# a78-flashcart-plus.net
KiCad netlist of a schematic drawn in EAGLE
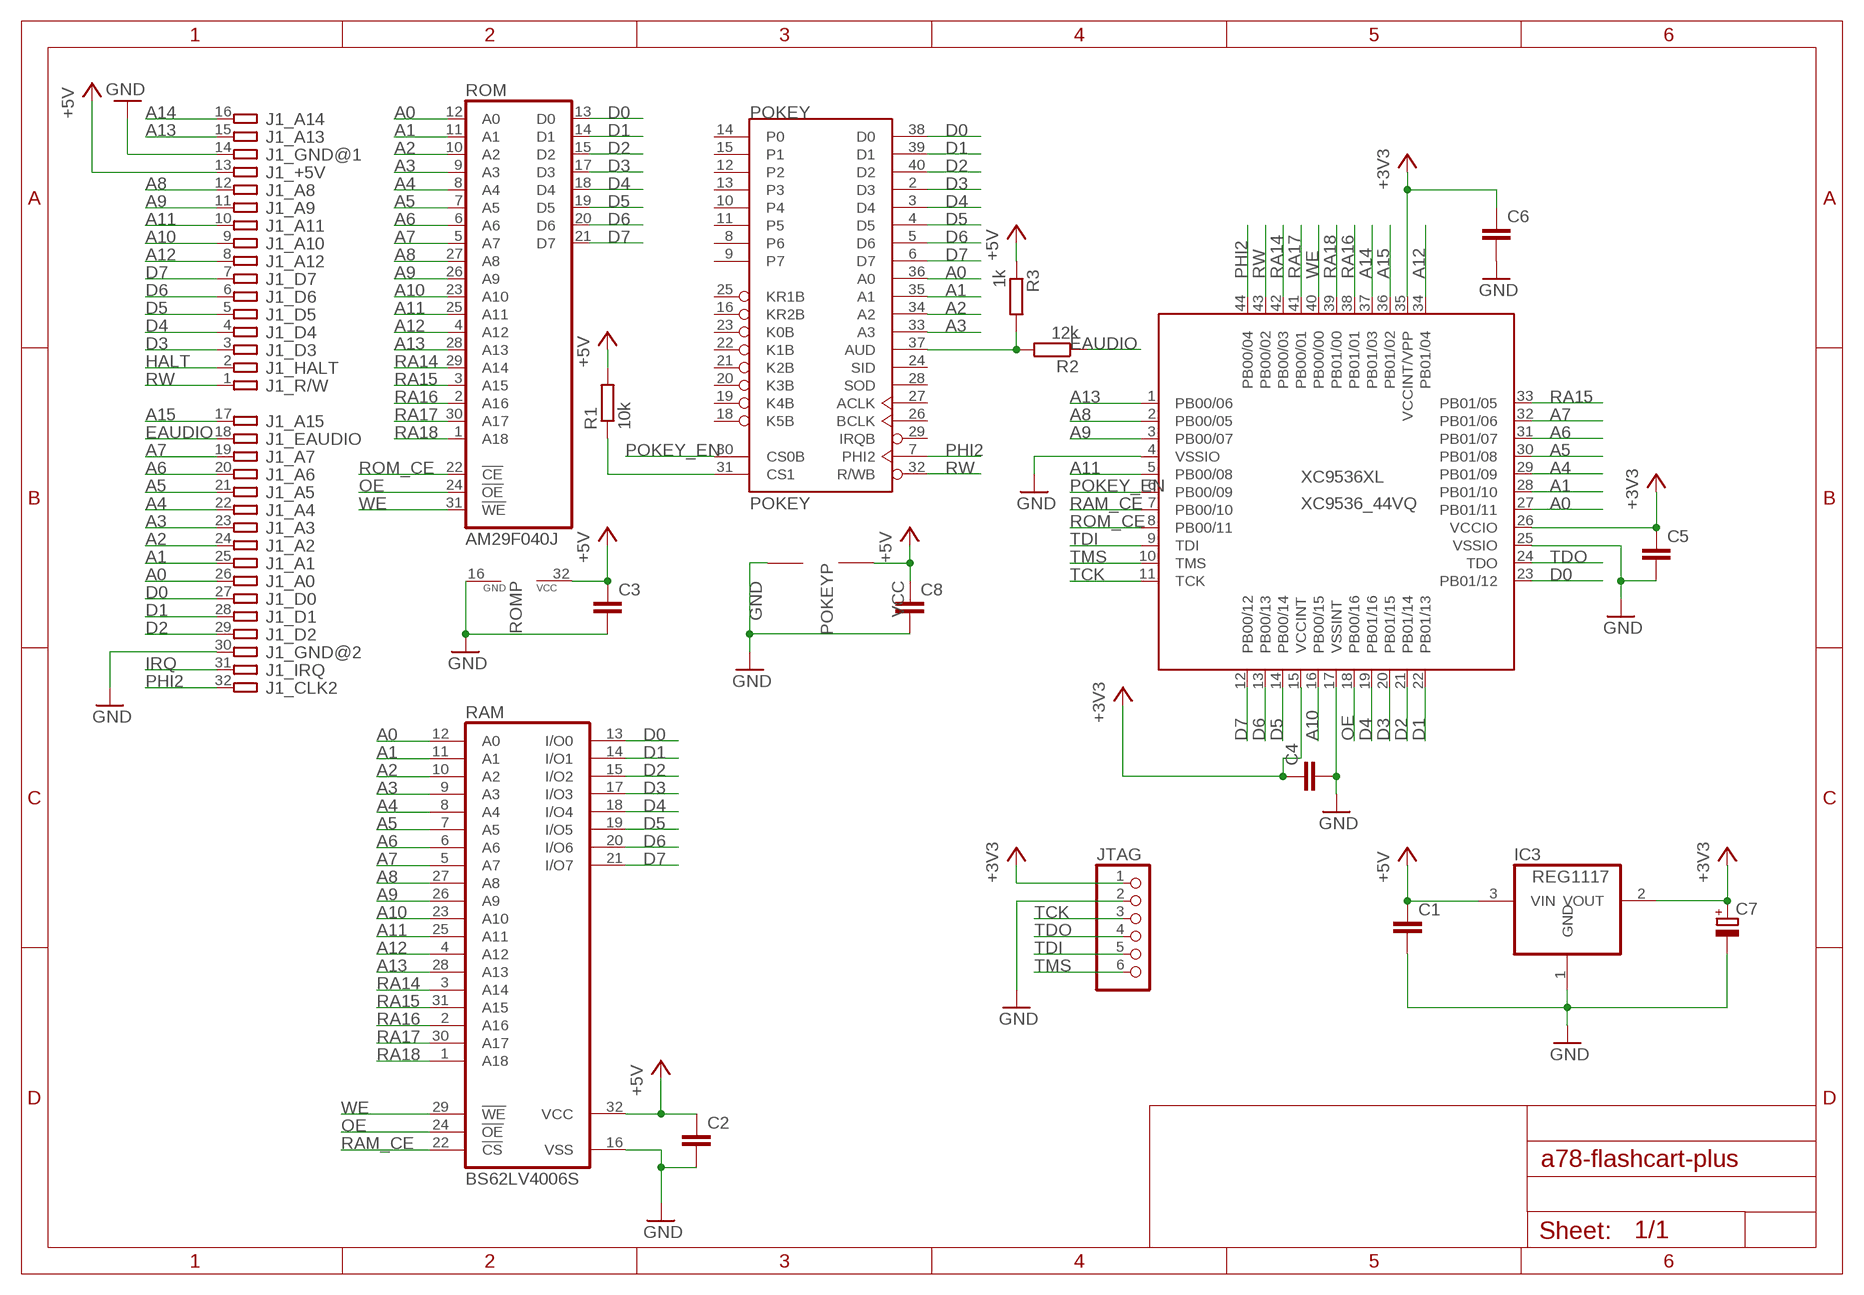
[diagram p0: schematic, sheet 1]

(export (version "E")
  (design (tool "Eeschema 10.0.6"))
  (components
    (comp (ref "C1")
      (value "C-EUC0603")
      (footprint "eagle-import:C0603")
      (libsource (lib "eagle-import") (part "C-EUC0603"))
    )
    (comp (ref "C2")
      (value "C-EUC0603")
      (footprint "eagle-import:C0603")
      (libsource (lib "eagle-import") (part "C-EUC0603"))
    )
    (comp (ref "C3")
      (value "C-EUC0603")
      (footprint "eagle-import:C0603")
      (libsource (lib "eagle-import") (part "C-EUC0603"))
    )
    (comp (ref "C4")
      (value "C-EUC0603")
      (footprint "eagle-import:C0603")
      (libsource (lib "eagle-import") (part "C-EUC0603"))
    )
    (comp (ref "C5")
      (value "C-EUC0603")
      (footprint "eagle-import:C0603")
      (libsource (lib "eagle-import") (part "C-EUC0603"))
    )
    (comp (ref "C6")
      (value "C-EUC0603")
      (footprint "eagle-import:C0603")
      (libsource (lib "eagle-import") (part "C-EUC0603"))
    )
    (comp (ref "C7")
      (value "CPOL-EUSMCC")
      (footprint "eagle-import:SMC_C")
      (libsource (lib "eagle-import") (part "CPOL-EUSMCC"))
    )
    (comp (ref "C8")
      (value "C-EUC0603")
      (footprint "eagle-import:C0603")
      (libsource (lib "eagle-import") (part "C-EUC0603"))
    )
    (comp (ref "IC3")
      (value "REG1117")
      (footprint "eagle-import:SOT223")
      (libsource (lib "eagle-import") (part "REG1117"))
    )
    (comp (ref "J1")
      (value "ATARI-7800-LARGE")
      (footprint "eagle-import:ATARI-7800-LARGE")
      (libsource (lib "eagle-import") (part "ATARI-7800-LARGE"))
    )
    (comp (ref "JTAG")
      (value "PINHD-1X6")
      (footprint "eagle-import:1X06")
      (libsource (lib "eagle-import") (part "PINHD-1X6"))
    )
    (comp (ref "POKEY")
      (value "POKEY")
      (footprint "eagle-import:DIL40")
      (libsource (lib "eagle-import") (part "POKEY"))
    )
    (comp (ref "R1")
      (value "10k")
      (footprint "eagle-import:R0603")
      (libsource (lib "eagle-import") (part "R-EU_R0603"))
    )
    (comp (ref "R2")
      (value "12k")
      (footprint "eagle-import:R0603")
      (libsource (lib "eagle-import") (part "R-EU_R0603"))
    )
    (comp (ref "R3")
      (value "1k")
      (footprint "eagle-import:R0603")
      (libsource (lib "eagle-import") (part "R-EU_R0603"))
    )
    (comp (ref "RAM")
      (value "BS62LV4006S")
      (footprint "eagle-import:SOP-32")
      (libsource (lib "eagle-import") (part "BS62LV4006S"))
    )
    (comp (ref "ROM")
      (value "AM29F040J")
      (footprint "eagle-import:PLCC32R")
      (libsource (lib "eagle-import") (part "AM29F040J"))
    )
    (comp (ref "XC9536XL")
      (value "XC9536_44VQ")
      (footprint "eagle-import:SQFP-S-10X10-44")
      (fields (field (name "MPN") "XC9536-15VQG44C"))
      (libsource (lib "eagle-import") (part "XC9536_44VQ"))
    )
  )
  (nets
    (net (code "1") (name "+3V3") (class "Default")
      (node (ref "C4") (pin "1") (pinfunction "1_1") (pintype "passive"))
      (node (ref "C5") (pin "1") (pinfunction "1_1") (pintype "passive"))
      (node (ref "C6") (pin "1") (pinfunction "1_1") (pintype "passive"))
      (node (ref "C7") (pin "+") (pinfunction "+_+") (pintype "passive"))
      (node (ref "IC3") (pin "2") (pinfunction "VOUT_2") (pintype "output"))
      (node (ref "JTAG") (pin "1") (pinfunction "1_1") (pintype "passive"))
      (node (ref "XC9536XL") (pin "15") (pinfunction "VCCINT_15") (pintype "power_in"))
      (node (ref "XC9536XL") (pin "26") (pinfunction "VCCIO_26") (pintype "power_in"))
      (node (ref "XC9536XL") (pin "35") (pinfunction "VCCINT/VPP_35") (pintype "input"))
    )
    (net (code "2") (name "+5V") (class "Default")
      (node (ref "C1") (pin "1") (pinfunction "1_1") (pintype "passive"))
      (node (ref "C2") (pin "1") (pinfunction "1_1") (pintype "passive"))
      (node (ref "C3") (pin "1") (pinfunction "1_1") (pintype "passive"))
      (node (ref "C8") (pin "1") (pinfunction "1_1") (pintype "passive"))
      (node (ref "IC3") (pin "3") (pinfunction "VIN_3") (pintype "input"))
      (node (ref "J1") (pin "13") (pinfunction "P_13") (pintype "bidirectional"))
      (node (ref "POKEY") (pin "17") (pinfunction "VCC_17") (pintype "power_in"))
      (node (ref "R1") (pin "2") (pinfunction "2_2") (pintype "passive"))
      (node (ref "R3") (pin "1") (pinfunction "1_1") (pintype "passive"))
      (node (ref "RAM") (pin "32") (pinfunction "VCC_32") (pintype "power_in"))
      (node (ref "ROM") (pin "32") (pinfunction "VCC_32") (pintype "power_in"))
    )
    (net (code "3") (name "/A0") (class "Default")
      (node (ref "J1") (pin "26") (pinfunction "P_26") (pintype "bidirectional"))
      (node (ref "POKEY") (pin "36") (pinfunction "A0_36") (pintype "bidirectional"))
      (node (ref "RAM") (pin "12") (pinfunction "A0_12") (pintype "input"))
      (node (ref "ROM") (pin "12") (pinfunction "A0_12") (pintype "input"))
      (node (ref "XC9536XL") (pin "27") (pinfunction "PB01/11_27") (pintype "bidirectional"))
    )
    (net (code "4") (name "/A1") (class "Default")
      (node (ref "J1") (pin "25") (pinfunction "P_25") (pintype "bidirectional"))
      (node (ref "POKEY") (pin "35") (pinfunction "A1_35") (pintype "bidirectional"))
      (node (ref "RAM") (pin "11") (pinfunction "A1_11") (pintype "input"))
      (node (ref "ROM") (pin "11") (pinfunction "A1_11") (pintype "input"))
      (node (ref "XC9536XL") (pin "28") (pinfunction "PB01/10_28") (pintype "bidirectional"))
    )
    (net (code "5") (name "/A2") (class "Default")
      (node (ref "J1") (pin "24") (pinfunction "P_24") (pintype "bidirectional"))
      (node (ref "POKEY") (pin "34") (pinfunction "A2_34") (pintype "bidirectional"))
      (node (ref "RAM") (pin "10") (pinfunction "A2_10") (pintype "input"))
      (node (ref "ROM") (pin "10") (pinfunction "A2_10") (pintype "input"))
    )
    (net (code "6") (name "/A3") (class "Default")
      (node (ref "J1") (pin "23") (pinfunction "P_23") (pintype "bidirectional"))
      (node (ref "POKEY") (pin "33") (pinfunction "A3_33") (pintype "bidirectional"))
      (node (ref "RAM") (pin "9") (pinfunction "A3_9") (pintype "input"))
      (node (ref "ROM") (pin "9") (pinfunction "A3_9") (pintype "input"))
    )
    (net (code "7") (name "/A4") (class "Default")
      (node (ref "J1") (pin "22") (pinfunction "P_22") (pintype "bidirectional"))
      (node (ref "RAM") (pin "8") (pinfunction "A4_8") (pintype "input"))
      (node (ref "ROM") (pin "8") (pinfunction "A4_8") (pintype "input"))
      (node (ref "XC9536XL") (pin "29") (pinfunction "PB01/09_29") (pintype "bidirectional"))
    )
    (net (code "8") (name "/A5") (class "Default")
      (node (ref "J1") (pin "21") (pinfunction "P_21") (pintype "bidirectional"))
      (node (ref "RAM") (pin "7") (pinfunction "A5_7") (pintype "input"))
      (node (ref "ROM") (pin "7") (pinfunction "A5_7") (pintype "input"))
      (node (ref "XC9536XL") (pin "30") (pinfunction "PB01/08_30") (pintype "bidirectional"))
    )
    (net (code "9") (name "/A6") (class "Default")
      (node (ref "J1") (pin "20") (pinfunction "P_20") (pintype "bidirectional"))
      (node (ref "RAM") (pin "6") (pinfunction "A6_6") (pintype "input"))
      (node (ref "ROM") (pin "6") (pinfunction "A6_6") (pintype "input"))
      (node (ref "XC9536XL") (pin "31") (pinfunction "PB01/07_31") (pintype "bidirectional"))
    )
    (net (code "10") (name "/A7") (class "Default")
      (node (ref "J1") (pin "19") (pinfunction "P_19") (pintype "bidirectional"))
      (node (ref "RAM") (pin "5") (pinfunction "A7_5") (pintype "input"))
      (node (ref "ROM") (pin "5") (pinfunction "A7_5") (pintype "input"))
      (node (ref "XC9536XL") (pin "32") (pinfunction "PB01/06_32") (pintype "bidirectional"))
    )
    (net (code "11") (name "/A8") (class "Default")
      (node (ref "J1") (pin "12") (pinfunction "P_12") (pintype "bidirectional"))
      (node (ref "RAM") (pin "27") (pinfunction "A8_27") (pintype "input"))
      (node (ref "ROM") (pin "27") (pinfunction "A8_27") (pintype "input"))
      (node (ref "XC9536XL") (pin "2") (pinfunction "PB00/05_2") (pintype "bidirectional"))
    )
    (net (code "12") (name "/A9") (class "Default")
      (node (ref "J1") (pin "11") (pinfunction "P_11") (pintype "bidirectional"))
      (node (ref "RAM") (pin "26") (pinfunction "A9_26") (pintype "input"))
      (node (ref "ROM") (pin "26") (pinfunction "A9_26") (pintype "input"))
      (node (ref "XC9536XL") (pin "3") (pinfunction "PB00/07_3") (pintype "bidirectional"))
    )
    (net (code "13") (name "/A10") (class "Default")
      (node (ref "J1") (pin "9") (pinfunction "P_9") (pintype "bidirectional"))
      (node (ref "RAM") (pin "23") (pinfunction "A10_23") (pintype "input"))
      (node (ref "ROM") (pin "23") (pinfunction "A10_23") (pintype "input"))
      (node (ref "XC9536XL") (pin "16") (pinfunction "PB00/15_16") (pintype "bidirectional"))
    )
    (net (code "14") (name "/A11") (class "Default")
      (node (ref "J1") (pin "10") (pinfunction "P_10") (pintype "bidirectional"))
      (node (ref "RAM") (pin "25") (pinfunction "A11_25") (pintype "input"))
      (node (ref "ROM") (pin "25") (pinfunction "A11_25") (pintype "input"))
      (node (ref "XC9536XL") (pin "5") (pinfunction "PB00/08_5") (pintype "bidirectional"))
    )
    (net (code "15") (name "/A12") (class "Default")
      (node (ref "J1") (pin "8") (pinfunction "P_8") (pintype "bidirectional"))
      (node (ref "RAM") (pin "4") (pinfunction "A12_4") (pintype "input"))
      (node (ref "ROM") (pin "4") (pinfunction "A12_4") (pintype "input"))
      (node (ref "XC9536XL") (pin "34") (pinfunction "PB01/04_34") (pintype "bidirectional"))
    )
    (net (code "16") (name "/A13") (class "Default")
      (node (ref "J1") (pin "15") (pinfunction "P_15") (pintype "bidirectional"))
      (node (ref "RAM") (pin "28") (pinfunction "A13_28") (pintype "input"))
      (node (ref "ROM") (pin "28") (pinfunction "A13_28") (pintype "input"))
      (node (ref "XC9536XL") (pin "1") (pinfunction "PB00/06_1") (pintype "bidirectional"))
    )
    (net (code "17") (name "/A14") (class "Default")
      (node (ref "J1") (pin "16") (pinfunction "P_16") (pintype "bidirectional"))
      (node (ref "XC9536XL") (pin "37") (pinfunction "PB01/03_37") (pintype "bidirectional"))
    )
    (net (code "18") (name "/A15") (class "Default")
      (node (ref "J1") (pin "17") (pinfunction "P_17") (pintype "bidirectional"))
      (node (ref "XC9536XL") (pin "36") (pinfunction "PB01/02_36") (pintype "bidirectional"))
    )
    (net (code "19") (name "/D0") (class "Default")
      (node (ref "J1") (pin "27") (pinfunction "P_27") (pintype "bidirectional"))
      (node (ref "POKEY") (pin "38") (pinfunction "D0_38") (pintype "bidirectional"))
      (node (ref "RAM") (pin "13") (pinfunction "I/O0_13") (pintype "bidirectional"))
      (node (ref "ROM") (pin "13") (pinfunction "D0_13") (pintype "tri_state"))
      (node (ref "XC9536XL") (pin "23") (pinfunction "PB01/12_23") (pintype "bidirectional"))
    )
    (net (code "20") (name "/D1") (class "Default")
      (node (ref "J1") (pin "28") (pinfunction "P_28") (pintype "bidirectional"))
      (node (ref "POKEY") (pin "39") (pinfunction "D1_39") (pintype "bidirectional"))
      (node (ref "RAM") (pin "14") (pinfunction "I/O1_14") (pintype "bidirectional"))
      (node (ref "ROM") (pin "14") (pinfunction "D1_14") (pintype "tri_state"))
      (node (ref "XC9536XL") (pin "22") (pinfunction "PB01/13_22") (pintype "bidirectional"))
    )
    (net (code "21") (name "/D2") (class "Default")
      (node (ref "J1") (pin "29") (pinfunction "P_29") (pintype "bidirectional"))
      (node (ref "POKEY") (pin "40") (pinfunction "D2_40") (pintype "bidirectional"))
      (node (ref "RAM") (pin "15") (pinfunction "I/O2_15") (pintype "bidirectional"))
      (node (ref "ROM") (pin "15") (pinfunction "D2_15") (pintype "tri_state"))
      (node (ref "XC9536XL") (pin "21") (pinfunction "PB01/14_21") (pintype "bidirectional"))
    )
    (net (code "22") (name "/D3") (class "Default")
      (node (ref "J1") (pin "3") (pinfunction "P_3") (pintype "bidirectional"))
      (node (ref "POKEY") (pin "2") (pinfunction "D3_2") (pintype "bidirectional"))
      (node (ref "RAM") (pin "17") (pinfunction "I/O3_17") (pintype "bidirectional"))
      (node (ref "ROM") (pin "17") (pinfunction "D3_17") (pintype "tri_state"))
      (node (ref "XC9536XL") (pin "20") (pinfunction "PB01/15_20") (pintype "bidirectional"))
    )
    (net (code "23") (name "/D4") (class "Default")
      (node (ref "J1") (pin "4") (pinfunction "P_4") (pintype "bidirectional"))
      (node (ref "POKEY") (pin "3") (pinfunction "D4_3") (pintype "bidirectional"))
      (node (ref "RAM") (pin "18") (pinfunction "I/O4_18") (pintype "bidirectional"))
      (node (ref "ROM") (pin "18") (pinfunction "D4_18") (pintype "tri_state"))
      (node (ref "XC9536XL") (pin "19") (pinfunction "PB01/16_19") (pintype "bidirectional"))
    )
    (net (code "24") (name "/D5") (class "Default")
      (node (ref "J1") (pin "5") (pinfunction "P_5") (pintype "bidirectional"))
      (node (ref "POKEY") (pin "4") (pinfunction "D5_4") (pintype "bidirectional"))
      (node (ref "RAM") (pin "19") (pinfunction "I/O5_19") (pintype "bidirectional"))
      (node (ref "ROM") (pin "19") (pinfunction "D5_19") (pintype "tri_state"))
      (node (ref "XC9536XL") (pin "14") (pinfunction "PB00/14_14") (pintype "bidirectional"))
    )
    (net (code "25") (name "/D6") (class "Default")
      (node (ref "J1") (pin "6") (pinfunction "P_6") (pintype "bidirectional"))
      (node (ref "POKEY") (pin "5") (pinfunction "D6_5") (pintype "bidirectional"))
      (node (ref "RAM") (pin "20") (pinfunction "I/O6_20") (pintype "bidirectional"))
      (node (ref "ROM") (pin "20") (pinfunction "D6_20") (pintype "tri_state"))
      (node (ref "XC9536XL") (pin "13") (pinfunction "PB00/13_13") (pintype "bidirectional"))
    )
    (net (code "26") (name "/D7") (class "Default")
      (node (ref "J1") (pin "7") (pinfunction "P_7") (pintype "bidirectional"))
      (node (ref "POKEY") (pin "6") (pinfunction "D7_6") (pintype "bidirectional"))
      (node (ref "RAM") (pin "21") (pinfunction "I/O7_21") (pintype "bidirectional"))
      (node (ref "ROM") (pin "21") (pinfunction "D7_21") (pintype "tri_state"))
      (node (ref "XC9536XL") (pin "12") (pinfunction "PB00/12_12") (pintype "bidirectional"))
    )
    (net (code "27") (name "/EAUDIO") (class "Default")
      (node (ref "J1") (pin "18") (pinfunction "P_18") (pintype "bidirectional"))
      (node (ref "R2") (pin "1") (pinfunction "1_1") (pintype "passive"))
    )
    (net (code "28") (name "/HALT") (class "Default")
      (node (ref "J1") (pin "2") (pinfunction "P_2") (pintype "bidirectional"))
    )
    (net (code "29") (name "/IRQ") (class "Default")
      (node (ref "J1") (pin "31") (pinfunction "P_31") (pintype "bidirectional"))
    )
    (net (code "30") (name "/OE") (class "Default")
      (node (ref "RAM") (pin "24") (pinfunction "~{OE}_24") (pintype "input"))
      (node (ref "ROM") (pin "24") (pinfunction "~{OE}_24") (pintype "input"))
      (node (ref "XC9536XL") (pin "18") (pinfunction "PB00/16_18") (pintype "bidirectional"))
    )
    (net (code "31") (name "/PHI2") (class "Default")
      (node (ref "J1") (pin "32") (pinfunction "P_32") (pintype "bidirectional"))
      (node (ref "POKEY") (pin "7") (pinfunction "PHI2_7") (pintype "input"))
      (node (ref "XC9536XL") (pin "44") (pinfunction "PB00/04_44") (pintype "bidirectional"))
    )
    (net (code "32") (name "/POKEY_EN") (class "Default")
      (node (ref "POKEY") (pin "30") (pinfunction "CS0B_30") (pintype "input"))
      (node (ref "XC9536XL") (pin "6") (pinfunction "PB00/09_6") (pintype "bidirectional"))
    )
    (net (code "33") (name "/RA14") (class "Default")
      (node (ref "RAM") (pin "3") (pinfunction "A14_3") (pintype "input"))
      (node (ref "ROM") (pin "29") (pinfunction "A14_29") (pintype "input"))
      (node (ref "XC9536XL") (pin "42") (pinfunction "PB00/03_42") (pintype "bidirectional"))
    )
    (net (code "34") (name "/RA15") (class "Default")
      (node (ref "RAM") (pin "31") (pinfunction "A15_31") (pintype "input"))
      (node (ref "ROM") (pin "3") (pinfunction "A15_3") (pintype "input"))
      (node (ref "XC9536XL") (pin "33") (pinfunction "PB01/05_33") (pintype "bidirectional"))
    )
    (net (code "35") (name "/RA16") (class "Default")
      (node (ref "RAM") (pin "2") (pinfunction "A16_2") (pintype "input"))
      (node (ref "ROM") (pin "2") (pinfunction "A16_2") (pintype "input"))
      (node (ref "XC9536XL") (pin "38") (pinfunction "PB01/01_38") (pintype "bidirectional"))
    )
    (net (code "36") (name "/RA17") (class "Default")
      (node (ref "RAM") (pin "30") (pinfunction "A17_30") (pintype "input"))
      (node (ref "ROM") (pin "30") (pinfunction "A17_30") (pintype "input"))
      (node (ref "XC9536XL") (pin "41") (pinfunction "PB00/01_41") (pintype "bidirectional"))
    )
    (net (code "37") (name "/RA18") (class "Default")
      (node (ref "RAM") (pin "1") (pinfunction "A18_1") (pintype "input"))
      (node (ref "ROM") (pin "1") (pinfunction "A18_1") (pintype "input"))
      (node (ref "XC9536XL") (pin "39") (pinfunction "PB01/00_39") (pintype "bidirectional"))
    )
    (net (code "38") (name "/RAM_CE") (class "Default")
      (node (ref "RAM") (pin "22") (pinfunction "~{CS}_22") (pintype "input"))
      (node (ref "XC9536XL") (pin "7") (pinfunction "PB00/10_7") (pintype "bidirectional"))
    )
    (net (code "39") (name "/ROM_CE") (class "Default")
      (node (ref "ROM") (pin "22") (pinfunction "~{CE}_22") (pintype "input"))
      (node (ref "XC9536XL") (pin "8") (pinfunction "PB00/11_8") (pintype "bidirectional"))
    )
    (net (code "40") (name "/RW") (class "Default")
      (node (ref "J1") (pin "1") (pinfunction "P_1") (pintype "bidirectional"))
      (node (ref "POKEY") (pin "32") (pinfunction "R/WB_32") (pintype "input"))
      (node (ref "XC9536XL") (pin "43") (pinfunction "PB00/02_43") (pintype "bidirectional"))
    )
    (net (code "41") (name "/TCK") (class "Default")
      (node (ref "JTAG") (pin "3") (pinfunction "3_3") (pintype "passive"))
      (node (ref "XC9536XL") (pin "11") (pinfunction "TCK_11") (pintype "input"))
    )
    (net (code "42") (name "/TDI") (class "Default")
      (node (ref "JTAG") (pin "5") (pinfunction "5_5") (pintype "passive"))
      (node (ref "XC9536XL") (pin "9") (pinfunction "TDI_9") (pintype "input"))
    )
    (net (code "43") (name "/TDO") (class "Default")
      (node (ref "JTAG") (pin "4") (pinfunction "4_4") (pintype "passive"))
      (node (ref "XC9536XL") (pin "24") (pinfunction "TDO_24") (pintype "output"))
    )
    (net (code "44") (name "/TMS") (class "Default")
      (node (ref "JTAG") (pin "6") (pinfunction "6_6") (pintype "passive"))
      (node (ref "XC9536XL") (pin "10") (pinfunction "TMS_10") (pintype "input"))
    )
    (net (code "45") (name "/WE") (class "Default")
      (node (ref "RAM") (pin "29") (pinfunction "~{WE}_29") (pintype "input"))
      (node (ref "ROM") (pin "31") (pinfunction "~{WE}_31") (pintype "input"))
      (node (ref "XC9536XL") (pin "40") (pinfunction "PB00/00_40") (pintype "bidirectional"))
    )
    (net (code "46") (name "GND") (class "Default")
      (node (ref "C1") (pin "2") (pinfunction "2_2") (pintype "passive"))
      (node (ref "C2") (pin "2") (pinfunction "2_2") (pintype "passive"))
      (node (ref "C3") (pin "2") (pinfunction "2_2") (pintype "passive"))
      (node (ref "C4") (pin "2") (pinfunction "2_2") (pintype "passive"))
      (node (ref "C5") (pin "2") (pinfunction "2_2") (pintype "passive"))
      (node (ref "C6") (pin "2") (pinfunction "2_2") (pintype "passive"))
      (node (ref "C7") (pin "-") (pinfunction "-_-") (pintype "passive"))
      (node (ref "C8") (pin "2") (pinfunction "2_2") (pintype "passive"))
      (node (ref "IC3") (pin "1") (pinfunction "GND_1") (pintype "power_in"))
      (node (ref "J1") (pin "14") (pinfunction "P_14") (pintype "bidirectional"))
      (node (ref "J1") (pin "30") (pinfunction "P_30") (pintype "bidirectional"))
      (node (ref "JTAG") (pin "2") (pinfunction "2_2") (pintype "passive"))
      (node (ref "POKEY") (pin "1") (pinfunction "GND_1") (pintype "power_in"))
      (node (ref "RAM") (pin "16") (pinfunction "VSS_16") (pintype "power_in"))
      (node (ref "ROM") (pin "16") (pinfunction "GND_16") (pintype "power_in"))
      (node (ref "XC9536XL") (pin "17") (pinfunction "VSSINT_17") (pintype "power_in"))
      (node (ref "XC9536XL") (pin "25") (pinfunction "VSSIO_25") (pintype "power_in"))
      (node (ref "XC9536XL") (pin "4") (pinfunction "VSSIO_4") (pintype "power_in"))
    )
    (net (code "47") (name "Net-(POKEYA-AUD)") (class "Default")
      (node (ref "POKEY") (pin "37") (pinfunction "AUD_37") (pintype "output"))
      (node (ref "R2") (pin "2") (pinfunction "2_2") (pintype "passive"))
      (node (ref "R3") (pin "2") (pinfunction "2_2") (pintype "passive"))
    )
    (net (code "48") (name "Net-(POKEYA-CS1)") (class "Default")
      (node (ref "POKEY") (pin "31") (pinfunction "CS1_31") (pintype "input"))
      (node (ref "R1") (pin "1") (pinfunction "1_1") (pintype "passive"))
    )
    (net (code "49") (name "unconnected-(POKEYA-ACLK-Pad27)") (class "Default")
      (node (ref "POKEY") (pin "27") (pinfunction "ACLK_27") (pintype "output"))
    )
    (net (code "50") (name "unconnected-(POKEYA-BCLK-Pad26)") (class "Default")
      (node (ref "POKEY") (pin "26") (pinfunction "BCLK_26") (pintype "bidirectional"))
    )
    (net (code "51") (name "unconnected-(POKEYA-IRQB-Pad29)") (class "Default")
      (node (ref "POKEY") (pin "29") (pinfunction "IRQB_29") (pintype "output"))
    )
    (net (code "52") (name "unconnected-(POKEYA-K0B-Pad23)") (class "Default")
      (node (ref "POKEY") (pin "23") (pinfunction "K0B_23") (pintype "input"))
    )
    (net (code "53") (name "unconnected-(POKEYA-K1B-Pad22)") (class "Default")
      (node (ref "POKEY") (pin "22") (pinfunction "K1B_22") (pintype "input"))
    )
    (net (code "54") (name "unconnected-(POKEYA-K2B-Pad21)") (class "Default")
      (node (ref "POKEY") (pin "21") (pinfunction "K2B_21") (pintype "input"))
    )
    (net (code "55") (name "unconnected-(POKEYA-K3B-Pad20)") (class "Default")
      (node (ref "POKEY") (pin "20") (pinfunction "K3B_20") (pintype "input"))
    )
    (net (code "56") (name "unconnected-(POKEYA-K4B-Pad19)") (class "Default")
      (node (ref "POKEY") (pin "19") (pinfunction "K4B_19") (pintype "input"))
    )
    (net (code "57") (name "unconnected-(POKEYA-K5B-Pad18)") (class "Default")
      (node (ref "POKEY") (pin "18") (pinfunction "K5B_18") (pintype "input"))
    )
    (net (code "58") (name "unconnected-(POKEYA-KR1B-Pad25)") (class "Default")
      (node (ref "POKEY") (pin "25") (pinfunction "KR1B_25") (pintype "output"))
    )
    (net (code "59") (name "unconnected-(POKEYA-KR2B-Pad16)") (class "Default")
      (node (ref "POKEY") (pin "16") (pinfunction "KR2B_16") (pintype "output"))
    )
    (net (code "60") (name "unconnected-(POKEYA-P0-Pad14)") (class "Default")
      (node (ref "POKEY") (pin "14") (pinfunction "P0_14") (pintype "input"))
    )
    (net (code "61") (name "unconnected-(POKEYA-P1-Pad15)") (class "Default")
      (node (ref "POKEY") (pin "15") (pinfunction "P1_15") (pintype "input"))
    )
    (net (code "62") (name "unconnected-(POKEYA-P2-Pad12)") (class "Default")
      (node (ref "POKEY") (pin "12") (pinfunction "P2_12") (pintype "input"))
    )
    (net (code "63") (name "unconnected-(POKEYA-P3-Pad13)") (class "Default")
      (node (ref "POKEY") (pin "13") (pinfunction "P3_13") (pintype "input"))
    )
    (net (code "64") (name "unconnected-(POKEYA-P4-Pad10)") (class "Default")
      (node (ref "POKEY") (pin "10") (pinfunction "P4_10") (pintype "input"))
    )
    (net (code "65") (name "unconnected-(POKEYA-P5-Pad11)") (class "Default")
      (node (ref "POKEY") (pin "11") (pinfunction "P5_11") (pintype "input"))
    )
    (net (code "66") (name "unconnected-(POKEYA-P6-Pad8)") (class "Default")
      (node (ref "POKEY") (pin "8") (pinfunction "P6_8") (pintype "input"))
    )
    (net (code "67") (name "unconnected-(POKEYA-P7-Pad9)") (class "Default")
      (node (ref "POKEY") (pin "9") (pinfunction "P7_9") (pintype "input"))
    )
    (net (code "68") (name "unconnected-(POKEYA-SID-Pad24)") (class "Default")
      (node (ref "POKEY") (pin "24") (pinfunction "SID_24") (pintype "input"))
    )
    (net (code "69") (name "unconnected-(POKEYA-SOD-Pad28)") (class "Default")
      (node (ref "POKEY") (pin "28") (pinfunction "SOD_28") (pintype "output"))
    )
  )
)
